# Top.net
KiCad netlist of a schematic drawn in Altium Designer
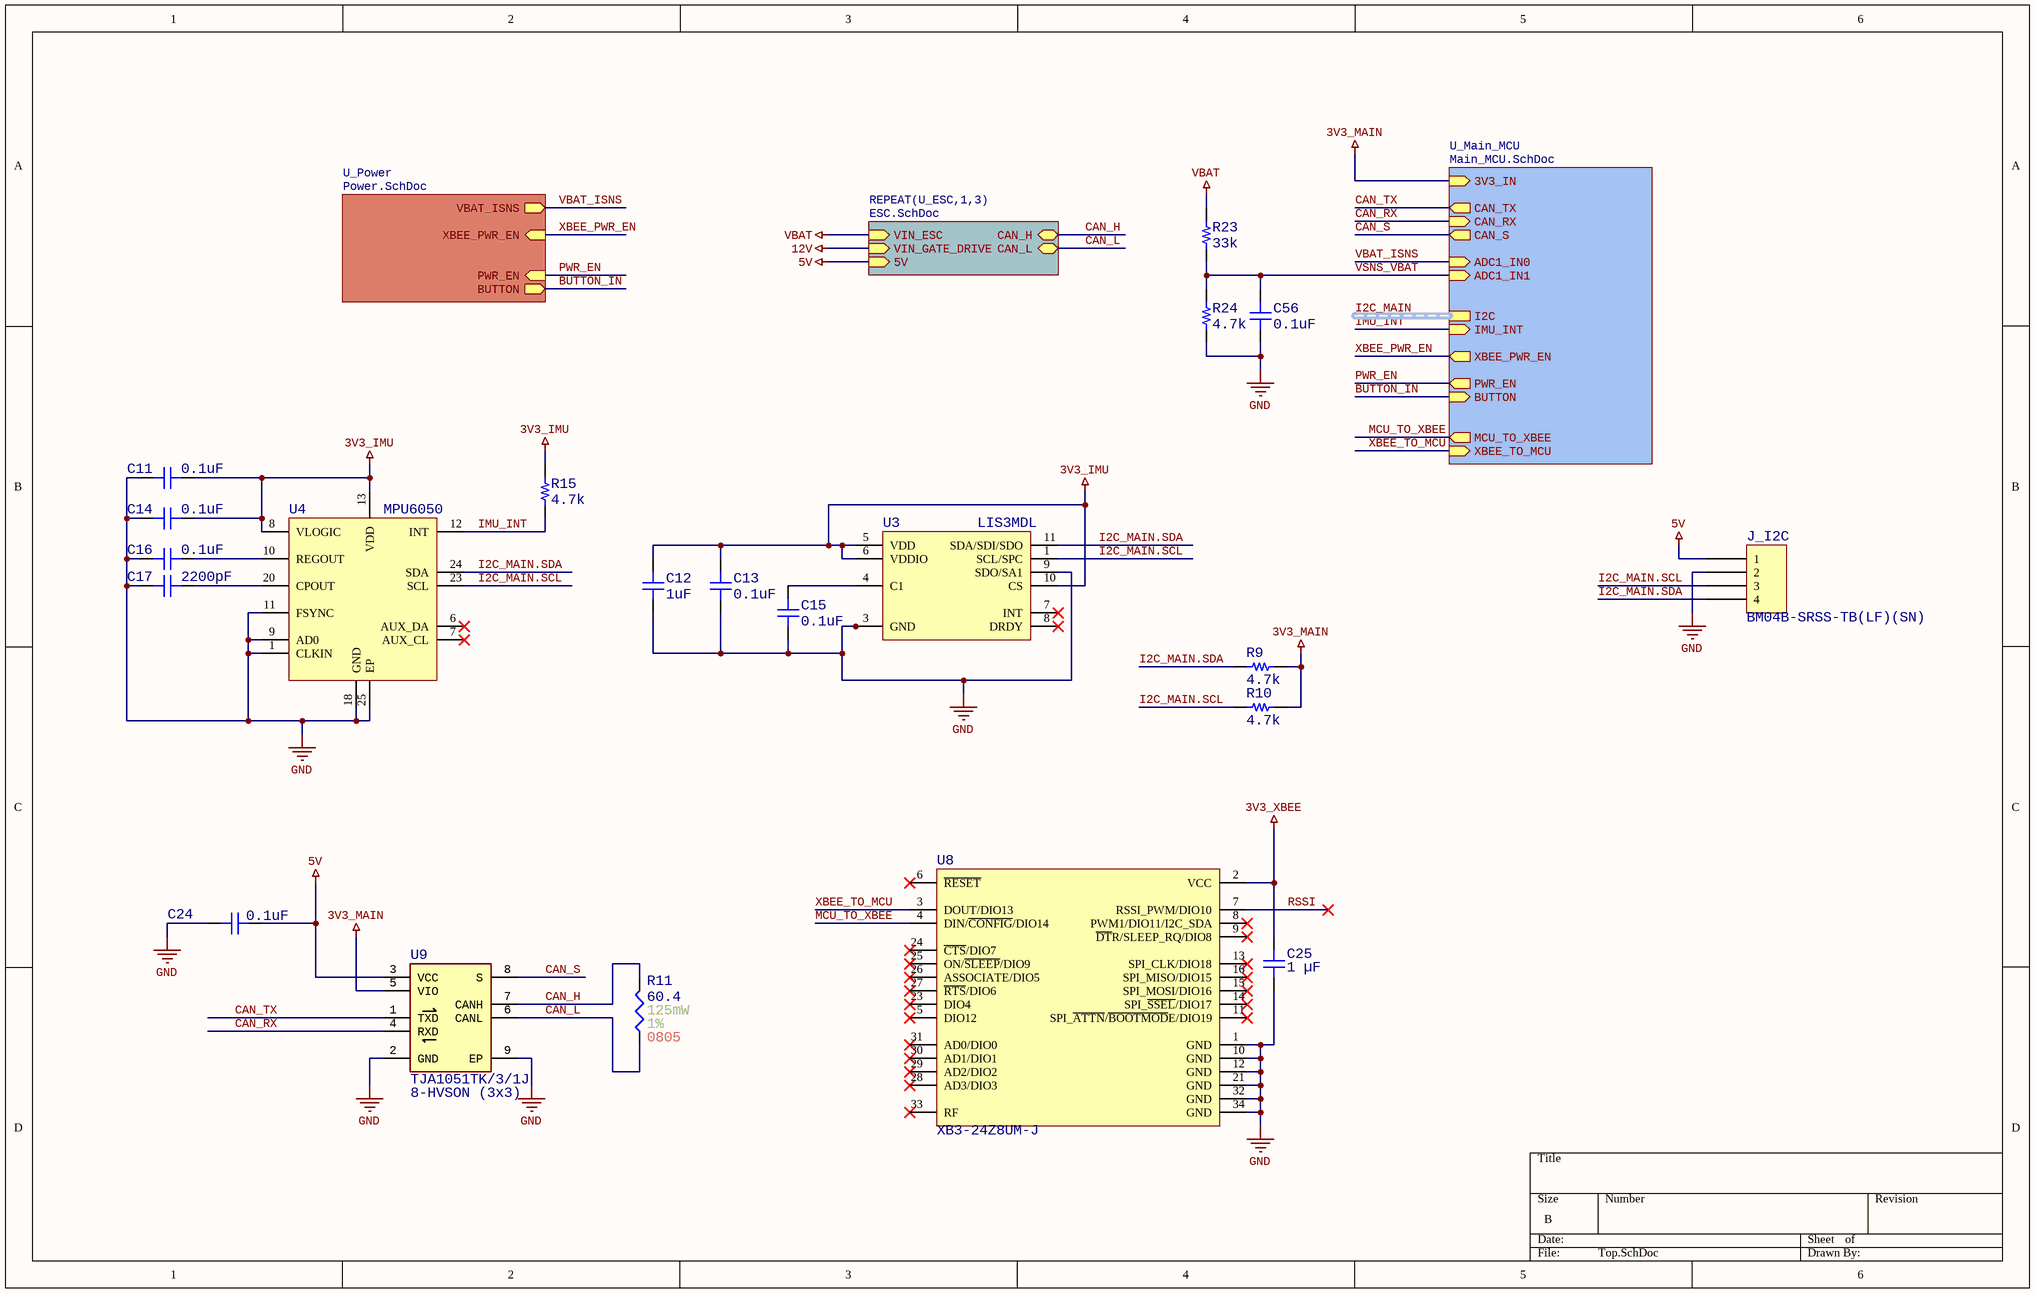
[diagram p0: Top.SchDoc]

(export (version "E")
  (design (tool "Eeschema 10.0.6"))
  (components
    (comp (ref "C11")
      (value "0.1uF")
      (footprint "CAP_0402")
      (description "CAP CER 402")
      (libsource (lib "IC") (part "CAP_0402"))
    )
    (comp (ref "C12")
      (value "1uF")
      (footprint "CAP_0402")
      (description "CAP CER 402")
      (libsource (lib "IC") (part "CAP_0402"))
    )
    (comp (ref "C13")
      (value "0.1uF")
      (footprint "CAP_0402")
      (description "CAP CER 402")
      (libsource (lib "IC") (part "CAP_0402"))
    )
    (comp (ref "C14")
      (value "0.1uF")
      (footprint "CAP_0402")
      (description "CAP CER 402")
      (libsource (lib "IC") (part "CAP_0402"))
    )
    (comp (ref "C15")
      (value "0.1uF")
      (footprint "CAP_0402")
      (description "CAP CER 402")
      (libsource (lib "IC") (part "CAP_0402"))
    )
    (comp (ref "C16")
      (value "0.1uF")
      (footprint "CAP_0402")
      (description "CAP CER 402")
      (libsource (lib "IC") (part "CAP_0402"))
    )
    (comp (ref "C17")
      (value "2200pF")
      (footprint "CAP_0402")
      (description "CAP CER 402")
      (libsource (lib "IC") (part "CAP_0402"))
    )
    (comp (ref "C24")
      (value "0.1uF")
      (footprint "CAP_0402")
      (description "CAP CER 402")
      (libsource (lib "IC") (part "CAP_0402"))
    )
    (comp (ref "C25")
      (value "1 µF")
      (footprint "CAP 0402_1005")
      (description "CAP CER 0.1UF 16V X7R 0402")
      (fields (field (name "PART NUMBER") "C0402C104K4RACAUTO") (field (name "MANUFACTURER") "KEMET"))
      (libsource (lib "Celestial Altium Library - altium_library") (part "Capacitor"))
    )
    (comp (ref "C56")
      (value "0.1uF")
      (footprint "CAP_0402")
      (description "CAP CER 402")
      (libsource (lib "IC") (part "CAP_0402"))
    )
    (comp (ref "J_I2C")
      (value "BM04B-SRSS-TB(LF)(SN)")
      (footprint "JST BM04B-SRSS-TB")
      (description "CONN HEADER SMD 4POS 1MM")
      (fields (field (name "MANUFACTURER") "JST Sales America Inc."))
      (libsource (lib "Celestial Altium Library - altium_library") (part "4 Pin"))
    )
    (comp (ref "R9")
      (value "4.7k")
      (footprint "RES_0402")
      (description "RES 0402")
      (libsource (lib "IC") (part "RES_0402"))
    )
    (comp (ref "R10")
      (value "4.7k")
      (footprint "RES_0402")
      (description "RES 0402")
      (libsource (lib "IC") (part "RES_0402"))
    )
    (comp (ref "R11")
      (value "60.4")
      (footprint "0805 Resistor")
      (description "Res 60.4 Ohm 1% 1/8W 0805")
      (fields
        (field (name "POWER") "125mW")
        (field (name "TOLERANCE") "1%")
        (field (name "CASE/PACKAGE") "0805")
        (field (name "MANUFACTURER PART NUMBER") "TFA0805R60R4F-T5")
      )
      (libsource (lib "Raise Robotics") (part "Resistor"))
    )
    (comp (ref "R15")
      (value "4.7k")
      (footprint "RES_0402")
      (description "RES 0402")
      (libsource (lib "IC") (part "RES_0402"))
    )
    (comp (ref "R23")
      (value "33k")
      (footprint "RES_0402")
      (description "RES 0402")
      (libsource (lib "IC") (part "RES_0402"))
    )
    (comp (ref "R24")
      (value "4.7k")
      (footprint "RES_0402")
      (description "RES 0402")
      (libsource (lib "IC") (part "RES_0402"))
    )
    (comp (ref "U3")
      (value "LIS3MDL")
      (footprint "LGA12_ST")
      (description "Magnetometer")
      (libsource (lib "IC") (part "LIS3MDL"))
    )
    (comp (ref "U4") (value "MPU6050") (footprint "IC_MPU6050") (libsource (lib "IC") (part "MPU6050")))
    (comp (ref "U8")
      (value "XB3-24Z8UM-J")
      (footprint "XCVR_XB3-24Z8UM-J")
      (description "802.15.4 Zigbee Transceiver Module 2.4GHz Antenna Not Included, U.FL Surface Mount")
      (fields (field (name "MF") "Digi International"))
      (libsource (lib "IC") (part "XB3-24Z8UM-J"))
    )
    (comp (ref "U9")
      (value "TJA1051TK/3/1J")
      (footprint "TJA1044xxK")
      (description "Interface Circuit, PDSO8")
      (fields (field (name "CASE/PACKAGE") "8-HVSON (3x3)"))
      (libsource (lib "Raise Robotics") (part "TJA1044"))
    )
  )
  (nets
    (net (code "3") (name "/CAN_H") (class "Default")
      (node (ref "R11") (pin "2") (pinfunction "2_2") (pintype "passive"))
      (node (ref "U9") (pin "7") (pinfunction "CANH_7") (pintype "passive"))
    )
    (net (code "4") (name "/CAN_L") (class "Default")
      (node (ref "R11") (pin "1") (pinfunction "1_1") (pintype "passive"))
      (node (ref "U9") (pin "6") (pinfunction "CANL_6") (pintype "passive"))
    )
    (net (code "5") (name "/CAN_RX") (class "Default")
      (node (ref "U9") (pin "4") (pinfunction "RXD_4") (pintype "passive"))
    )
    (net (code "6") (name "/CAN_S") (class "Default")
      (node (ref "U9") (pin "8") (pinfunction "S_8") (pintype "passive"))
    )
    (net (code "7") (name "/CAN_TX") (class "Default")
      (node (ref "U9") (pin "1") (pinfunction "TXD_1") (pintype "passive"))
    )
    (net (code "8") (name "/I2C_MAIN.SCL") (class "Default")
      (node (ref "J_I2C") (pin "3") (pinfunction "3_3") (pintype "passive"))
      (node (ref "R10") (pin "2") (pinfunction "2_2") (pintype "passive"))
      (node (ref "U3") (pin "1") (pinfunction "SCL/SPC_1") (pintype "passive"))
      (node (ref "U4") (pin "23") (pinfunction "SCL_23") (pintype "passive"))
    )
    (net (code "9") (name "/I2C_MAIN.SDA") (class "Default")
      (node (ref "J_I2C") (pin "4") (pinfunction "4_4") (pintype "passive"))
      (node (ref "R9") (pin "2") (pinfunction "2_2") (pintype "passive"))
      (node (ref "U3") (pin "11") (pinfunction "SDA/SDI/SDO_11") (pintype "passive"))
      (node (ref "U4") (pin "24") (pinfunction "SDA_24") (pintype "passive"))
    )
    (net (code "10") (name "/IMU_INT") (class "Default")
      (node (ref "R15") (pin "2") (pinfunction "2_2") (pintype "passive"))
      (node (ref "U4") (pin "12") (pinfunction "INT_12") (pintype "passive"))
    )
    (net (code "11") (name "/MCU_TO_XBEE") (class "Default")
      (node (ref "U8") (pin "4") (pinfunction "DIN/~{CONFIG}/DIO14_4") (pintype "passive"))
    )
    (net (code "13") (name "/RSSI") (class "Default")
      (node (ref "U8") (pin "7") (pinfunction "RSSI_PWM/DIO10_7") (pintype "passive+no_connect"))
    )
    (net (code "15") (name "/VSNS_VBAT") (class "Default")
      (node (ref "C56") (pin "1") (pinfunction "1_1") (pintype "passive"))
      (node (ref "R23") (pin "2") (pinfunction "2_2") (pintype "passive"))
      (node (ref "R24") (pin "1") (pinfunction "1_1") (pintype "passive"))
    )
    (net (code "17") (name "/XBEE_TO_MCU") (class "Default")
      (node (ref "U8") (pin "3") (pinfunction "DOUT/DIO13_3") (pintype "passive"))
    )
    (net (code "19") (name "3V3_IMU") (class "Default")
      (node (ref "C11") (pin "1") (pinfunction "1_1") (pintype "passive"))
      (node (ref "C12") (pin "1") (pinfunction "1_1") (pintype "passive"))
      (node (ref "C13") (pin "1") (pinfunction "1_1") (pintype "passive"))
      (node (ref "C14") (pin "1") (pinfunction "1_1") (pintype "passive"))
      (node (ref "R15") (pin "1") (pinfunction "1_1") (pintype "passive"))
      (node (ref "U3") (pin "10") (pinfunction "CS_10") (pintype "passive"))
      (node (ref "U3") (pin "5") (pinfunction "VDD_5") (pintype "passive"))
      (node (ref "U3") (pin "6") (pinfunction "VDDIO_6") (pintype "passive"))
      (node (ref "U4") (pin "13") (pinfunction "VDD_13") (pintype "passive"))
      (node (ref "U4") (pin "8") (pinfunction "VLOGIC_8") (pintype "passive"))
    )
    (net (code "20") (name "3V3_MAIN") (class "Default")
      (node (ref "R10") (pin "1") (pinfunction "1_1") (pintype "passive"))
      (node (ref "R9") (pin "1") (pinfunction "1_1") (pintype "passive"))
      (node (ref "U9") (pin "5") (pinfunction "VIO_5") (pintype "passive"))
    )
    (net (code "21") (name "3V3_XBEE") (class "Default")
      (node (ref "C25") (pin "1") (pinfunction "1_1") (pintype "passive"))
      (node (ref "U8") (pin "2") (pinfunction "VCC_2") (pintype "passive"))
    )
    (net (code "22") (name "5V") (class "Default")
      (node (ref "C24") (pin "1") (pinfunction "1_1") (pintype "passive"))
      (node (ref "J_I2C") (pin "1") (pinfunction "1_1") (pintype "passive"))
      (node (ref "U9") (pin "3") (pinfunction "VCC_3") (pintype "passive"))
    )
    (net (code "24") (name "GND") (class "Default")
      (node (ref "C11") (pin "2") (pinfunction "2_2") (pintype "passive"))
      (node (ref "C12") (pin "2") (pinfunction "2_2") (pintype "passive"))
      (node (ref "C13") (pin "2") (pinfunction "2_2") (pintype "passive"))
      (node (ref "C14") (pin "2") (pinfunction "2_2") (pintype "passive"))
      (node (ref "C15") (pin "2") (pinfunction "2_2") (pintype "passive"))
      (node (ref "C16") (pin "2") (pinfunction "2_2") (pintype "passive"))
      (node (ref "C17") (pin "2") (pinfunction "2_2") (pintype "passive"))
      (node (ref "C24") (pin "2") (pinfunction "2_2") (pintype "passive"))
      (node (ref "C25") (pin "2") (pinfunction "2_2") (pintype "passive"))
      (node (ref "C56") (pin "2") (pinfunction "2_2") (pintype "passive"))
      (node (ref "J_I2C") (pin "2") (pinfunction "2_2") (pintype "passive"))
      (node (ref "R24") (pin "2") (pinfunction "2_2") (pintype "passive"))
      (node (ref "U3") (pin "12") (pinfunction "Reserved_12") (pintype "passive"))
      (node (ref "U3") (pin "2") (pinfunction "Reserved_2") (pintype "passive"))
      (node (ref "U3") (pin "3") (pinfunction "GND_3") (pintype "passive"))
      (node (ref "U3") (pin "9") (pinfunction "SDO/SA1_9") (pintype "passive"))
      (node (ref "U4") (pin "1") (pinfunction "CLKIN_1") (pintype "passive"))
      (node (ref "U4") (pin "11") (pinfunction "FSYNC_11") (pintype "passive"))
      (node (ref "U4") (pin "18") (pinfunction "GND_18") (pintype "passive"))
      (node (ref "U4") (pin "25") (pinfunction "EP_25") (pintype "passive"))
      (node (ref "U4") (pin "9") (pinfunction "AD0_9") (pintype "passive"))
      (node (ref "U8") (pin "1") (pinfunction "GND_1") (pintype "passive"))
      (node (ref "U8") (pin "10") (pinfunction "GND_10") (pintype "passive"))
      (node (ref "U8") (pin "12") (pinfunction "GND_12") (pintype "passive"))
      (node (ref "U8") (pin "21") (pinfunction "GND_21") (pintype "passive"))
      (node (ref "U8") (pin "32") (pinfunction "GND_32") (pintype "passive"))
      (node (ref "U8") (pin "34") (pinfunction "GND_34") (pintype "passive"))
      (node (ref "U9") (pin "2") (pinfunction "GND_2") (pintype "passive"))
      (node (ref "U9") (pin "9") (pinfunction "EP_9") (pintype "passive"))
    )
    (net (code "25") (name "Net-(U3-C1)") (class "Default")
      (node (ref "C15") (pin "1") (pinfunction "1_1") (pintype "passive"))
      (node (ref "U3") (pin "4") (pinfunction "C1_4") (pintype "passive"))
    )
    (net (code "26") (name "Net-(U4-CPOUT)") (class "Default")
      (node (ref "C17") (pin "1") (pinfunction "1_1") (pintype "passive"))
      (node (ref "U4") (pin "20") (pinfunction "CPOUT_20") (pintype "passive"))
    )
    (net (code "27") (name "Net-(U4-REGOUT)") (class "Default")
      (node (ref "C16") (pin "1") (pinfunction "1_1") (pintype "passive"))
      (node (ref "U4") (pin "10") (pinfunction "REGOUT_10") (pintype "passive"))
    )
    (net (code "28") (name "VBAT") (class "Default")
      (node (ref "R23") (pin "1") (pinfunction "1_1") (pintype "passive"))
    )
    (net (code "29") (name "unconnected-(U3-DRDY-Pad8)") (class "Default")
      (node (ref "U3") (pin "8") (pinfunction "DRDY_8") (pintype "passive+no_connect"))
    )
    (net (code "30") (name "unconnected-(U3-INT-Pad7)") (class "Default")
      (node (ref "U3") (pin "7") (pinfunction "INT_7") (pintype "passive+no_connect"))
    )
    (net (code "31") (name "unconnected-(U4-AUX_CL-Pad7)") (class "Default")
      (node (ref "U4") (pin "7") (pinfunction "AUX_CL_7") (pintype "passive+no_connect"))
    )
    (net (code "32") (name "unconnected-(U4-AUX_DA-Pad6)") (class "Default")
      (node (ref "U4") (pin "6") (pinfunction "AUX_DA_6") (pintype "passive+no_connect"))
    )
    (net (code "33") (name "unconnected-(U8-AD0{slash}DIO0-Pad31)") (class "Default")
      (node (ref "U8") (pin "31") (pinfunction "AD0/DIO0_31") (pintype "passive+no_connect"))
    )
    (net (code "34") (name "unconnected-(U8-AD1{slash}DIO1-Pad30)") (class "Default")
      (node (ref "U8") (pin "30") (pinfunction "AD1/DIO1_30") (pintype "passive+no_connect"))
    )
    (net (code "35") (name "unconnected-(U8-AD2{slash}DIO2-Pad29)") (class "Default")
      (node (ref "U8") (pin "29") (pinfunction "AD2/DIO2_29") (pintype "passive+no_connect"))
    )
    (net (code "36") (name "unconnected-(U8-AD3{slash}DIO3-Pad28)") (class "Default")
      (node (ref "U8") (pin "28") (pinfunction "AD3/DIO3_28") (pintype "passive+no_connect"))
    )
    (net (code "37") (name "unconnected-(U8-ASSOCIATE{slash}DIO5-Pad26)") (class "Default")
      (node (ref "U8") (pin "26") (pinfunction "ASSOCIATE/DIO5_26") (pintype "passive+no_connect"))
    )
    (net (code "38") (name "unconnected-(U8-DIO4-Pad23)") (class "Default")
      (node (ref "U8") (pin "23") (pinfunction "DIO4_23") (pintype "passive+no_connect"))
    )
    (net (code "39") (name "unconnected-(U8-DIO12-Pad5)") (class "Default")
      (node (ref "U8") (pin "5") (pinfunction "DIO12_5") (pintype "passive+no_connect"))
    )
    (net (code "40") (name "unconnected-(U8-ON{slash}~{SLEEP}{slash}DIO9-Pad25)") (class "Default")
      (node (ref "U8") (pin "25") (pinfunction "ON/~{SLEEP}/DIO9_25") (pintype "passive+no_connect"))
    )
    (net (code "41") (name "unconnected-(U8-PWM1{slash}DIO11{slash}I2C_SDA-Pad8)") (class "Default")
      (node (ref "U8") (pin "8") (pinfunction "PWM1/DIO11/I2C_SDA_8") (pintype "passive+no_connect"))
    )
    (net (code "42") (name "unconnected-(U8-RF-Pad33)") (class "Default")
      (node (ref "U8") (pin "33") (pinfunction "RF_33") (pintype "passive+no_connect"))
    )
    (net (code "43") (name "unconnected-(U8-SPI_CLK{slash}DIO18-Pad13)") (class "Default")
      (node (ref "U8") (pin "13") (pinfunction "SPI_CLK/DIO18_13") (pintype "passive+no_connect"))
    )
    (net (code "44") (name "unconnected-(U8-SPI_MISO{slash}DIO15-Pad16)") (class "Default")
      (node (ref "U8") (pin "16") (pinfunction "SPI_MISO/DIO15_16") (pintype "passive+no_connect"))
    )
    (net (code "45") (name "unconnected-(U8-SPI_MOSI{slash}DIO16-Pad15)") (class "Default")
      (node (ref "U8") (pin "15") (pinfunction "SPI_MOSI/DIO16_15") (pintype "passive+no_connect"))
    )
    (net (code "46") (name "unconnected-(U8-SPI_~{ATTN}{slash}~{BOOTMOD}E{slash}DIO19-Pad11)") (class "Default")
      (node (ref "U8") (pin "11") (pinfunction "SPI_~{ATTN}/~{BOOTMOD}E/DIO19_11") (pintype "passive+no_connect"))
    )
    (net (code "47") (name "unconnected-(U8-SPI_~{SSEL}{slash}DIO17-Pad14)") (class "Default")
      (node (ref "U8") (pin "14") (pinfunction "SPI_~{SSEL}/DIO17_14") (pintype "passive+no_connect"))
    )
    (net (code "48") (name "unconnected-(U8-~{CTS}{slash}DIO7-Pad24)") (class "Default")
      (node (ref "U8") (pin "24") (pinfunction "~{CTS}/DIO7_24") (pintype "passive+no_connect"))
    )
    (net (code "49") (name "unconnected-(U8-~{DT}R{slash}SLEEP_RQ{slash}DIO8-Pad9)") (class "Default")
      (node (ref "U8") (pin "9") (pinfunction "~{DT}R/SLEEP_RQ/DIO8_9") (pintype "passive+no_connect"))
    )
    (net (code "50") (name "unconnected-(U8-~{RESET}-Pad6)") (class "Default")
      (node (ref "U8") (pin "6") (pinfunction "~{RESET}_6") (pintype "passive+no_connect"))
    )
    (net (code "51") (name "unconnected-(U8-~{RTS}{slash}DIO6-Pad27)") (class "Default")
      (node (ref "U8") (pin "27") (pinfunction "~{RTS}/DIO6_27") (pintype "passive+no_connect"))
    )
  )
)
